# mm16.net
KiCad netlist of a schematic drawn in EAGLE
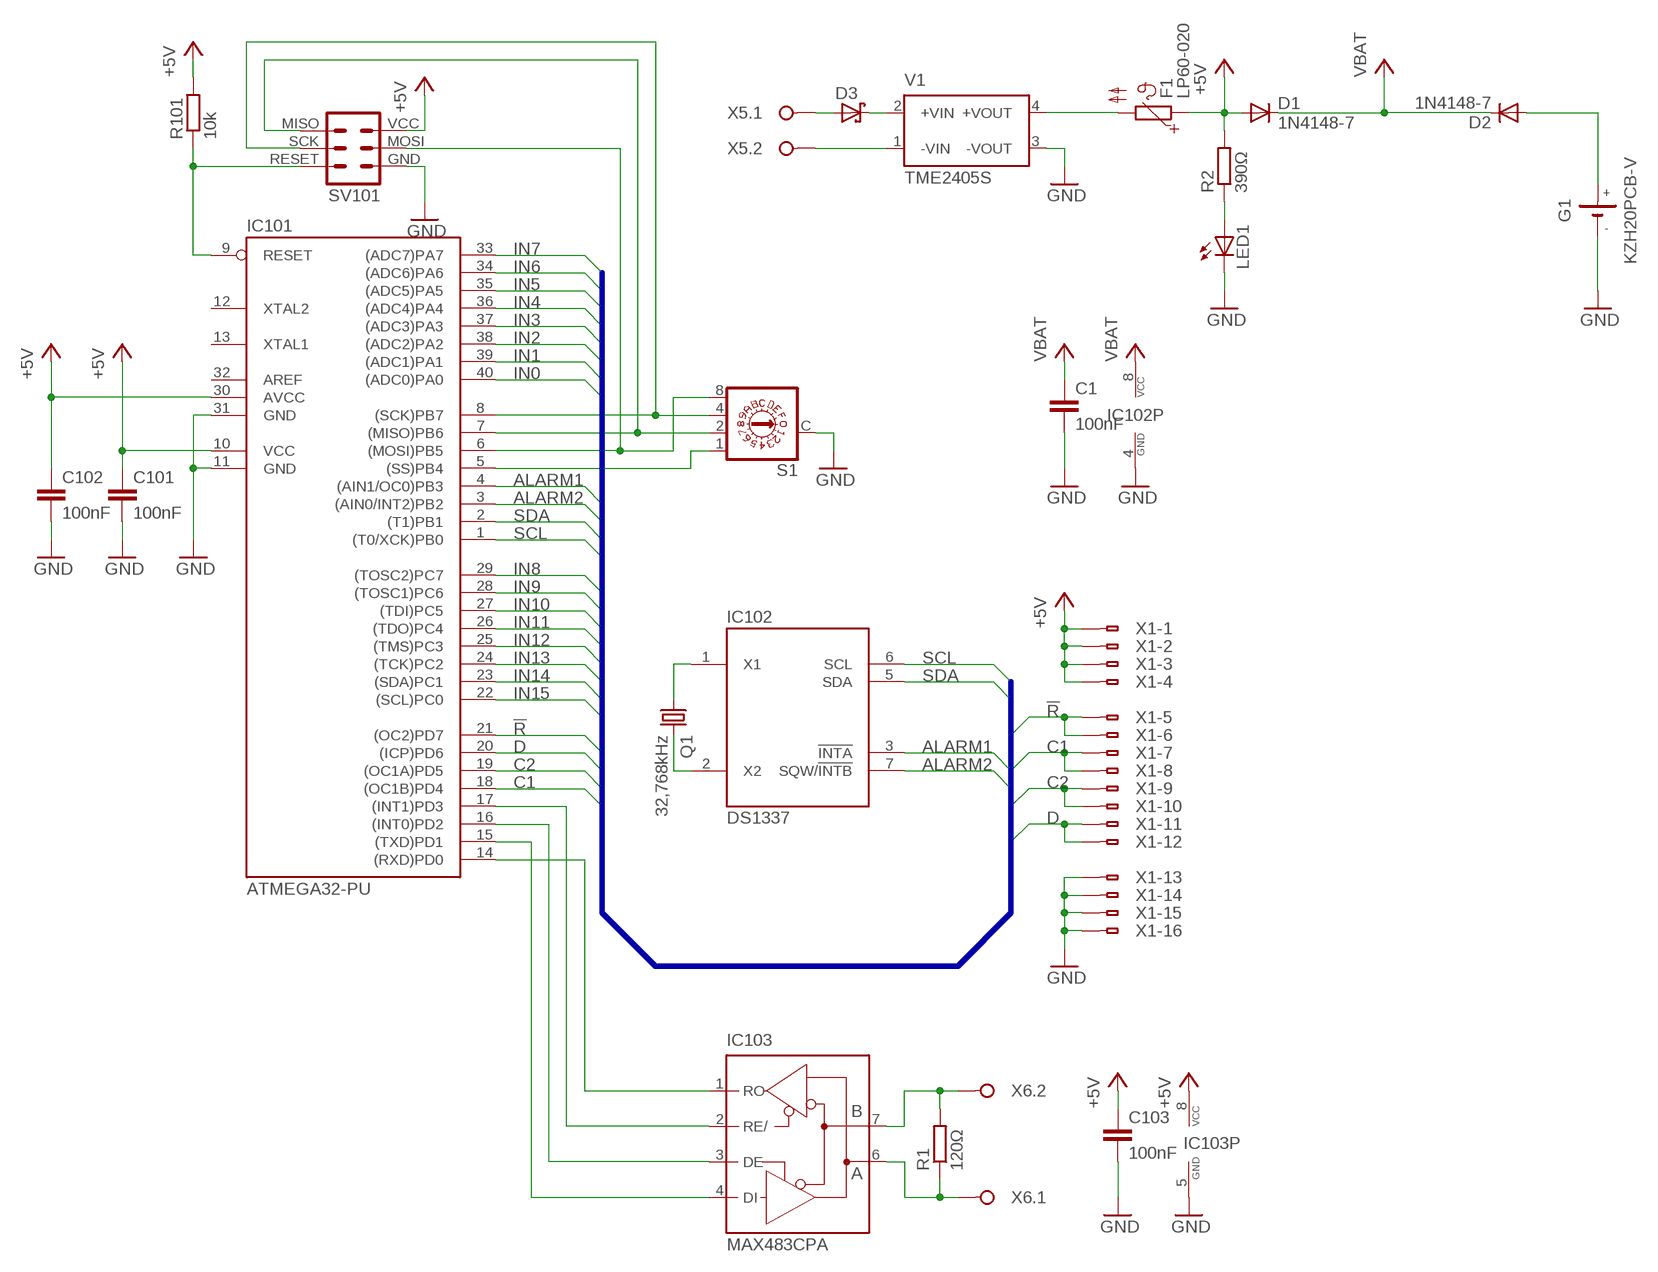
[diagram p0: schematic, sheet 1]
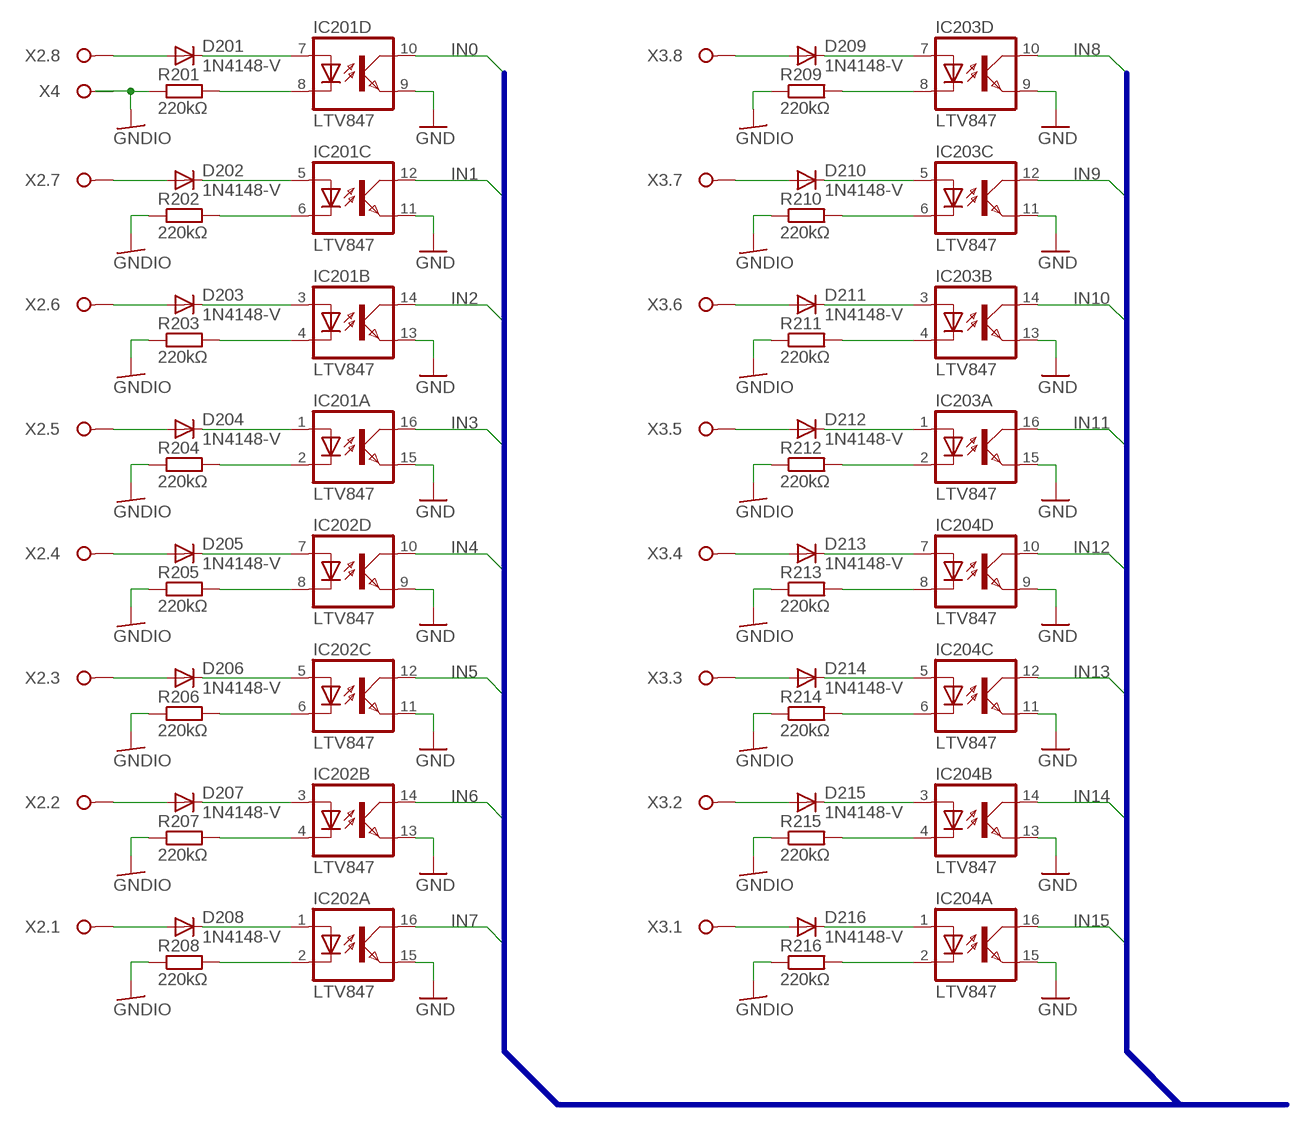
[diagram p1: schematic, sheet 2]

(export (version "E")
  (design (tool "Eeschema 10.0.6"))
  (components
    (comp (ref "C1")
      (value "100nF")
      (footprint "eagle-import:C025-025X050")
      (libsource (lib "eagle-import") (part "C_025-025X050"))
    )
    (comp (ref "C101")
      (value "100nF")
      (footprint "eagle-import:C025-025X050")
      (libsource (lib "eagle-import") (part "C_025-025X050"))
    )
    (comp (ref "C102")
      (value "100nF")
      (footprint "eagle-import:C025-025X050")
      (libsource (lib "eagle-import") (part "C_025-025X050"))
    )
    (comp (ref "C103")
      (value "100nF")
      (footprint "eagle-import:C025-025X050")
      (libsource (lib "eagle-import") (part "C_025-025X050"))
    )
    (comp (ref "D1")
      (value "1N4148-7")
      (footprint "eagle-import:DO35-7@1")
      (libsource (lib "eagle-import") (part "1N4148-7"))
    )
    (comp (ref "D2")
      (value "1N4148-7")
      (footprint "eagle-import:DO35-7@1")
      (libsource (lib "eagle-import") (part "1N4148-7"))
    )
    (comp (ref "D3")
      (value "SCHOTTKY-DIODEDO35-7")
      (footprint "eagle-import:DO35-7")
      (libsource (lib "eagle-import") (part "SCHOTTKY-DIODEDO35-7"))
    )
    (comp (ref "F1")
      (value "LP60-020")
      (footprint "eagle-import:LP60-020")
      (libsource (lib "eagle-import") (part "LP60-020"))
    )
    (comp (ref "G1")
      (value "KZH20PCB-V")
      (footprint "eagle-import:KZH20PCB-V")
      (libsource (lib "eagle-import") (part "KZH20PCB-V"))
    )
    (comp (ref "IC101")
      (value "ATMEGA32-PU")
      (footprint "eagle-import:DIL40")
      (libsource (lib "eagle-import") (part "ATMEGA32-PU"))
    )
    (comp (ref "IC102")
      (value "DS1337")
      (footprint "eagle-import:DIL08")
      (libsource (lib "eagle-import") (part "DS1337"))
    )
    (comp (ref "IC103")
      (value "MAX483CPA")
      (footprint "eagle-import:DIL08")
      (libsource (lib "eagle-import") (part "MAX48CPA3"))
    )
    (comp (ref "LED1")
      (value "LED3MM")
      (footprint "eagle-import:LED3MM")
      (libsource (lib "eagle-import") (part "LED3MM"))
    )
    (comp (ref "Q1")
      (value "32,768kHz")
      (footprint "eagle-import:TC38H")
      (libsource (lib "eagle-import") (part "Q_TC38H"))
    )
    (comp (ref "R1")
      (value "120Ω")
      (footprint "eagle-import:0204V")
      (libsource (lib "eagle-import") (part "R_0204/2V"))
    )
    (comp (ref "R2")
      (value "390Ω")
      (footprint "eagle-import:0204V")
      (libsource (lib "eagle-import") (part "R_0204/2V"))
    )
    (comp (ref "R101")
      (value "10k")
      (footprint "eagle-import:0204V")
      (libsource (lib "eagle-import") (part "R_0204/2V"))
    )
    (comp (ref "S1")
      (value "P103")
      (footprint "eagle-import:P103")
      (libsource (lib "eagle-import") (part "P103"))
    )
    (comp (ref "SV101")
      (value "AVR_ISP6")
      (footprint "eagle-import:ML6")
      (libsource (lib "eagle-import") (part "AVR_ISP6"))
    )
    (comp (ref "V1")
      (value "TME2405S")
      (footprint "eagle-import:TME-24V")
      (fields
        (field (name "MPN") "TME 2405S")
        (field (name "MPN_1") "TME 2405S")
        (field (name "OC_FARNELL") "1007547")
        (field (name "OC_NEWARK") "51R5329")
      )
      (libsource (lib "eagle-import") (part "TME?2405S"))
    )
    (comp (ref "X1")
      (value "WS16V")
      (footprint "eagle-import:WS16V")
      (libsource (lib "eagle-import") (part "WS16V"))
    )
    (comp (ref "X5")
      (value "WAGO_236-402")
      (footprint "eagle-import:WAGO_236-402")
      (libsource (lib "eagle-import") (part "WAGO_236-402"))
    )
    (comp (ref "X6")
      (value "WAGO_236-402")
      (footprint "eagle-import:WAGO_236-402")
      (libsource (lib "eagle-import") (part "WAGO_236-402"))
    )
    (comp (ref "D201")
      (value "1N4148-V")
      (footprint "eagle-import:DO35-V")
      (libsource (lib "eagle-import") (part "1N4148-V"))
    )
    (comp (ref "D202")
      (value "1N4148-V")
      (footprint "eagle-import:DO35-V")
      (libsource (lib "eagle-import") (part "1N4148-V"))
    )
    (comp (ref "D203")
      (value "1N4148-V")
      (footprint "eagle-import:DO35-V")
      (libsource (lib "eagle-import") (part "1N4148-V"))
    )
    (comp (ref "D204")
      (value "1N4148-V")
      (footprint "eagle-import:DO35-V")
      (libsource (lib "eagle-import") (part "1N4148-V"))
    )
    (comp (ref "D205")
      (value "1N4148-V")
      (footprint "eagle-import:DO35-V")
      (libsource (lib "eagle-import") (part "1N4148-V"))
    )
    (comp (ref "D206")
      (value "1N4148-V")
      (footprint "eagle-import:DO35-V")
      (libsource (lib "eagle-import") (part "1N4148-V"))
    )
    (comp (ref "D207")
      (value "1N4148-V")
      (footprint "eagle-import:DO35-V")
      (libsource (lib "eagle-import") (part "1N4148-V"))
    )
    (comp (ref "D208")
      (value "1N4148-V")
      (footprint "eagle-import:DO35-V")
      (libsource (lib "eagle-import") (part "1N4148-V"))
    )
    (comp (ref "D209")
      (value "1N4148-V")
      (footprint "eagle-import:DO35-V")
      (libsource (lib "eagle-import") (part "1N4148-V"))
    )
    (comp (ref "D210")
      (value "1N4148-V")
      (footprint "eagle-import:DO35-V")
      (libsource (lib "eagle-import") (part "1N4148-V"))
    )
    (comp (ref "D211")
      (value "1N4148-V")
      (footprint "eagle-import:DO35-V")
      (libsource (lib "eagle-import") (part "1N4148-V"))
    )
    (comp (ref "D212")
      (value "1N4148-V")
      (footprint "eagle-import:DO35-V")
      (libsource (lib "eagle-import") (part "1N4148-V"))
    )
    (comp (ref "D213")
      (value "1N4148-V")
      (footprint "eagle-import:DO35-V")
      (libsource (lib "eagle-import") (part "1N4148-V"))
    )
    (comp (ref "D214")
      (value "1N4148-V")
      (footprint "eagle-import:DO35-V")
      (libsource (lib "eagle-import") (part "1N4148-V"))
    )
    (comp (ref "D215")
      (value "1N4148-V")
      (footprint "eagle-import:DO35-V")
      (libsource (lib "eagle-import") (part "1N4148-V"))
    )
    (comp (ref "D216")
      (value "1N4148-V")
      (footprint "eagle-import:DO35-V")
      (libsource (lib "eagle-import") (part "1N4148-V"))
    )
    (comp (ref "IC201")
      (value "LTV847")
      (footprint "eagle-import:DIL16")
      (libsource (lib "eagle-import") (part "LTV847"))
    )
    (comp (ref "IC202")
      (value "LTV847")
      (footprint "eagle-import:DIL16")
      (libsource (lib "eagle-import") (part "LTV847"))
    )
    (comp (ref "IC203")
      (value "LTV847")
      (footprint "eagle-import:DIL16")
      (libsource (lib "eagle-import") (part "LTV847"))
    )
    (comp (ref "IC204")
      (value "LTV847")
      (footprint "eagle-import:DIL16")
      (libsource (lib "eagle-import") (part "LTV847"))
    )
    (comp (ref "R201")
      (value "220kΩ")
      (footprint "eagle-import:0204V")
      (libsource (lib "eagle-import") (part "R_0204/2V"))
    )
    (comp (ref "R202")
      (value "220kΩ")
      (footprint "eagle-import:0204V")
      (libsource (lib "eagle-import") (part "R_0204/2V"))
    )
    (comp (ref "R203")
      (value "220kΩ")
      (footprint "eagle-import:0204V")
      (libsource (lib "eagle-import") (part "R_0204/2V"))
    )
    (comp (ref "R204")
      (value "220kΩ")
      (footprint "eagle-import:0204V")
      (libsource (lib "eagle-import") (part "R_0204/2V"))
    )
    (comp (ref "R205")
      (value "220kΩ")
      (footprint "eagle-import:0204V")
      (libsource (lib "eagle-import") (part "R_0204/2V"))
    )
    (comp (ref "R206")
      (value "220kΩ")
      (footprint "eagle-import:0204V")
      (libsource (lib "eagle-import") (part "R_0204/2V"))
    )
    (comp (ref "R207")
      (value "220kΩ")
      (footprint "eagle-import:0204V")
      (libsource (lib "eagle-import") (part "R_0204/2V"))
    )
    (comp (ref "R208")
      (value "220kΩ")
      (footprint "eagle-import:0204V")
      (libsource (lib "eagle-import") (part "R_0204/2V"))
    )
    (comp (ref "R209")
      (value "220kΩ")
      (footprint "eagle-import:0204V")
      (libsource (lib "eagle-import") (part "R_0204/2V"))
    )
    (comp (ref "R210")
      (value "220kΩ")
      (footprint "eagle-import:0204V")
      (libsource (lib "eagle-import") (part "R_0204/2V"))
    )
    (comp (ref "R211")
      (value "220kΩ")
      (footprint "eagle-import:0204V")
      (libsource (lib "eagle-import") (part "R_0204/2V"))
    )
    (comp (ref "R212")
      (value "220kΩ")
      (footprint "eagle-import:0204V")
      (libsource (lib "eagle-import") (part "R_0204/2V"))
    )
    (comp (ref "R213")
      (value "220kΩ")
      (footprint "eagle-import:0204V")
      (libsource (lib "eagle-import") (part "R_0204/2V"))
    )
    (comp (ref "R214")
      (value "220kΩ")
      (footprint "eagle-import:0204V")
      (libsource (lib "eagle-import") (part "R_0204/2V"))
    )
    (comp (ref "R215")
      (value "220kΩ")
      (footprint "eagle-import:0204V")
      (libsource (lib "eagle-import") (part "R_0204/2V"))
    )
    (comp (ref "R216")
      (value "220kΩ")
      (footprint "eagle-import:0204V")
      (libsource (lib "eagle-import") (part "R_0204/2V"))
    )
    (comp (ref "X2")
      (value "WAGO_236-408")
      (footprint "eagle-import:WAGO_236-408")
      (libsource (lib "eagle-import") (part "WAGO_236-408"))
    )
    (comp (ref "X3")
      (value "WAGO_236-408")
      (footprint "eagle-import:WAGO_236-408")
      (libsource (lib "eagle-import") (part "WAGO_236-408"))
    )
    (comp (ref "X4")
      (value "WAGO_236-401")
      (footprint "eagle-import:WAGO_236-401")
      (libsource (lib "eagle-import") (part "WAGO_236-401"))
    )
  )
  (nets
    (net (code "1") (name "+5V") (class "Default")
      (node (ref "C101") (pin "1") (pinfunction "1_1") (pintype "passive"))
      (node (ref "C102") (pin "1") (pinfunction "1_1") (pintype "passive"))
      (node (ref "C103") (pin "1") (pinfunction "1_1") (pintype "passive"))
      (node (ref "D1") (pin "A") (pinfunction "A_A") (pintype "passive"))
      (node (ref "F1") (pin "P$1") (pinfunction "1_P$1") (pintype "passive"))
      (node (ref "IC101") (pin "10") (pinfunction "VCC_10") (pintype "power_in"))
      (node (ref "IC101") (pin "30") (pinfunction "AVCC_30") (pintype "power_in"))
      (node (ref "IC103") (pin "8") (pinfunction "VCC_8") (pintype "power_in"))
      (node (ref "R101") (pin "2") (pinfunction "2_2") (pintype "passive"))
      (node (ref "R2") (pin "2") (pinfunction "2_2") (pintype "passive"))
      (node (ref "SV101") (pin "VCC") (pinfunction "VCC_VCC") (pintype "passive"))
      (node (ref "X1") (pin "1") (pinfunction "A_1") (pintype "passive"))
      (node (ref "X1") (pin "2") (pinfunction "A_2") (pintype "passive"))
      (node (ref "X1") (pin "3") (pinfunction "A_3") (pintype "passive"))
      (node (ref "X1") (pin "4") (pinfunction "A_4") (pintype "passive"))
    )
    (net (code "2") (name "ALARM1") (class "Default")
      (node (ref "IC101") (pin "4") (pinfunction "(AIN1/OC0)PB3_4") (pintype "bidirectional"))
      (node (ref "IC102") (pin "3") (pinfunction "~{INTA}_3") (pintype "open_collector"))
    )
    (net (code "3") (name "ALARM2") (class "Default")
      (node (ref "IC101") (pin "3") (pinfunction "(AIN0/INT2)PB2_3") (pintype "bidirectional"))
      (node (ref "IC102") (pin "7") (pinfunction "SQW/~{INTB}_7") (pintype "open_collector"))
    )
    (net (code "4") (name "C1") (class "Default")
      (node (ref "IC101") (pin "18") (pinfunction "(OC1B)PD4_18") (pintype "bidirectional"))
      (node (ref "X1") (pin "7") (pinfunction "A_7") (pintype "passive"))
      (node (ref "X1") (pin "8") (pinfunction "A_8") (pintype "passive"))
    )
    (net (code "5") (name "C2") (class "Default")
      (node (ref "IC101") (pin "19") (pinfunction "(OC1A)PD5_19") (pintype "bidirectional"))
      (node (ref "X1") (pin "10") (pinfunction "A_10") (pintype "passive"))
      (node (ref "X1") (pin "9") (pinfunction "A_9") (pintype "passive"))
    )
    (net (code "6") (name "D") (class "Default")
      (node (ref "IC101") (pin "20") (pinfunction "(ICP)PD6_20") (pintype "bidirectional"))
      (node (ref "X1") (pin "11") (pinfunction "A_11") (pintype "passive"))
      (node (ref "X1") (pin "12") (pinfunction "A_12") (pintype "passive"))
    )
    (net (code "7") (name "GND") (class "Default")
      (node (ref "C1") (pin "2") (pinfunction "2_2") (pintype "passive"))
      (node (ref "C101") (pin "2") (pinfunction "2_2") (pintype "passive"))
      (node (ref "C102") (pin "2") (pinfunction "2_2") (pintype "passive"))
      (node (ref "C103") (pin "2") (pinfunction "2_2") (pintype "passive"))
      (node (ref "G1") (pin "-") (pinfunction "-_-") (pintype "passive"))
      (node (ref "IC101") (pin "11") (pinfunction "GND_11") (pintype "power_in"))
      (node (ref "IC101") (pin "31") (pinfunction "GND_31") (pintype "power_in"))
      (node (ref "IC102") (pin "4") (pinfunction "GND_4") (pintype "power_in"))
      (node (ref "IC103") (pin "5") (pinfunction "GND_5") (pintype "power_in"))
      (node (ref "IC201") (pin "11") (pinfunction "EMIT_11") (pintype "passive"))
      (node (ref "IC201") (pin "13") (pinfunction "EMIT_13") (pintype "passive"))
      (node (ref "IC201") (pin "15") (pinfunction "EMIT_15") (pintype "passive"))
      (node (ref "IC201") (pin "9") (pinfunction "EMIT_9") (pintype "passive"))
      (node (ref "IC202") (pin "11") (pinfunction "EMIT_11") (pintype "passive"))
      (node (ref "IC202") (pin "13") (pinfunction "EMIT_13") (pintype "passive"))
      (node (ref "IC202") (pin "15") (pinfunction "EMIT_15") (pintype "passive"))
      (node (ref "IC202") (pin "9") (pinfunction "EMIT_9") (pintype "passive"))
      (node (ref "IC203") (pin "11") (pinfunction "EMIT_11") (pintype "passive"))
      (node (ref "IC203") (pin "13") (pinfunction "EMIT_13") (pintype "passive"))
      (node (ref "IC203") (pin "15") (pinfunction "EMIT_15") (pintype "passive"))
      (node (ref "IC203") (pin "9") (pinfunction "EMIT_9") (pintype "passive"))
      (node (ref "IC204") (pin "11") (pinfunction "EMIT_11") (pintype "passive"))
      (node (ref "IC204") (pin "13") (pinfunction "EMIT_13") (pintype "passive"))
      (node (ref "IC204") (pin "15") (pinfunction "EMIT_15") (pintype "passive"))
      (node (ref "IC204") (pin "9") (pinfunction "EMIT_9") (pintype "passive"))
      (node (ref "LED1") (pin "K") (pinfunction "C_K") (pintype "passive"))
      (node (ref "S1") (pin "C") (pinfunction "C_C") (pintype "passive"))
      (node (ref "SV101") (pin "GND") (pinfunction "GND_GND") (pintype "passive"))
      (node (ref "V1") (pin "3") (pinfunction "-VOUT_3") (pintype "passive"))
      (node (ref "X1") (pin "13") (pinfunction "A_13") (pintype "passive"))
      (node (ref "X1") (pin "14") (pinfunction "A_14") (pintype "passive"))
      (node (ref "X1") (pin "15") (pinfunction "A_15") (pintype "passive"))
      (node (ref "X1") (pin "16") (pinfunction "A_16") (pintype "passive"))
    )
    (net (code "8") (name "GNDIO") (class "Default")
      (node (ref "R201") (pin "1") (pinfunction "1_1") (pintype "passive"))
      (node (ref "R202") (pin "1") (pinfunction "1_1") (pintype "passive"))
      (node (ref "R203") (pin "1") (pinfunction "1_1") (pintype "passive"))
      (node (ref "R204") (pin "1") (pinfunction "1_1") (pintype "passive"))
      (node (ref "R205") (pin "1") (pinfunction "1_1") (pintype "passive"))
      (node (ref "R206") (pin "1") (pinfunction "1_1") (pintype "passive"))
      (node (ref "R207") (pin "1") (pinfunction "1_1") (pintype "passive"))
      (node (ref "R208") (pin "1") (pinfunction "1_1") (pintype "passive"))
      (node (ref "R209") (pin "1") (pinfunction "1_1") (pintype "passive"))
      (node (ref "R210") (pin "1") (pinfunction "1_1") (pintype "passive"))
      (node (ref "R211") (pin "1") (pinfunction "1_1") (pintype "passive"))
      (node (ref "R212") (pin "1") (pinfunction "1_1") (pintype "passive"))
      (node (ref "R213") (pin "1") (pinfunction "1_1") (pintype "passive"))
      (node (ref "R214") (pin "1") (pinfunction "1_1") (pintype "passive"))
      (node (ref "R215") (pin "1") (pinfunction "1_1") (pintype "passive"))
      (node (ref "R216") (pin "1") (pinfunction "1_1") (pintype "passive"))
      (node (ref "X4") (pin "A1") (pinfunction "A_A1") (pintype "passive"))
      (node (ref "X4") (pin "B1") (pinfunction "B_B1") (pintype "passive"))
    )
    (net (code "9") (name "IN0") (class "Default")
      (node (ref "IC101") (pin "40") (pinfunction "(ADC0)PA0_40") (pintype "bidirectional"))
      (node (ref "IC201") (pin "10") (pinfunction "COL_10") (pintype "passive"))
    )
    (net (code "10") (name "IN1") (class "Default")
      (node (ref "IC101") (pin "39") (pinfunction "(ADC1)PA1_39") (pintype "bidirectional"))
      (node (ref "IC201") (pin "12") (pinfunction "COL_12") (pintype "passive"))
    )
    (net (code "11") (name "IN2") (class "Default")
      (node (ref "IC101") (pin "38") (pinfunction "(ADC2)PA2_38") (pintype "bidirectional"))
      (node (ref "IC201") (pin "14") (pinfunction "COL_14") (pintype "passive"))
    )
    (net (code "12") (name "IN3") (class "Default")
      (node (ref "IC101") (pin "37") (pinfunction "(ADC3)PA3_37") (pintype "bidirectional"))
      (node (ref "IC201") (pin "16") (pinfunction "COL_16") (pintype "passive"))
    )
    (net (code "13") (name "IN4") (class "Default")
      (node (ref "IC101") (pin "36") (pinfunction "(ADC4)PA4_36") (pintype "bidirectional"))
      (node (ref "IC202") (pin "10") (pinfunction "COL_10") (pintype "passive"))
    )
    (net (code "14") (name "IN5") (class "Default")
      (node (ref "IC101") (pin "35") (pinfunction "(ADC5)PA5_35") (pintype "bidirectional"))
      (node (ref "IC202") (pin "12") (pinfunction "COL_12") (pintype "passive"))
    )
    (net (code "15") (name "IN6") (class "Default")
      (node (ref "IC101") (pin "34") (pinfunction "(ADC6)PA6_34") (pintype "bidirectional"))
      (node (ref "IC202") (pin "14") (pinfunction "COL_14") (pintype "passive"))
    )
    (net (code "16") (name "IN7") (class "Default")
      (node (ref "IC101") (pin "33") (pinfunction "(ADC7)PA7_33") (pintype "bidirectional"))
      (node (ref "IC202") (pin "16") (pinfunction "COL_16") (pintype "passive"))
    )
    (net (code "17") (name "IN8") (class "Default")
      (node (ref "IC101") (pin "29") (pinfunction "(TOSC2)PC7_29") (pintype "bidirectional"))
      (node (ref "IC203") (pin "10") (pinfunction "COL_10") (pintype "passive"))
    )
    (net (code "18") (name "IN9") (class "Default")
      (node (ref "IC101") (pin "28") (pinfunction "(TOSC1)PC6_28") (pintype "bidirectional"))
      (node (ref "IC203") (pin "12") (pinfunction "COL_12") (pintype "passive"))
    )
    (net (code "19") (name "IN10") (class "Default")
      (node (ref "IC101") (pin "27") (pinfunction "(TDI)PC5_27") (pintype "bidirectional"))
      (node (ref "IC203") (pin "14") (pinfunction "COL_14") (pintype "passive"))
    )
    (net (code "20") (name "IN11") (class "Default")
      (node (ref "IC101") (pin "26") (pinfunction "(TDO)PC4_26") (pintype "bidirectional"))
      (node (ref "IC203") (pin "16") (pinfunction "COL_16") (pintype "passive"))
    )
    (net (code "21") (name "IN12") (class "Default")
      (node (ref "IC101") (pin "25") (pinfunction "(TMS)PC3_25") (pintype "bidirectional"))
      (node (ref "IC204") (pin "10") (pinfunction "COL_10") (pintype "passive"))
    )
    (net (code "22") (name "IN13") (class "Default")
      (node (ref "IC101") (pin "24") (pinfunction "(TCK)PC2_24") (pintype "bidirectional"))
      (node (ref "IC204") (pin "12") (pinfunction "COL_12") (pintype "passive"))
    )
    (net (code "23") (name "IN14") (class "Default")
      (node (ref "IC101") (pin "23") (pinfunction "(SDA)PC1_23") (pintype "bidirectional"))
      (node (ref "IC204") (pin "14") (pinfunction "COL_14") (pintype "passive"))
    )
    (net (code "24") (name "IN15") (class "Default")
      (node (ref "IC101") (pin "22") (pinfunction "(SCL)PC0_22") (pintype "bidirectional"))
      (node (ref "IC204") (pin "16") (pinfunction "COL_16") (pintype "passive"))
    )
    (net (code "25") (name "Net-(D2-PadA)") (class "Default")
      (node (ref "D2") (pin "A") (pinfunction "A_A") (pintype "passive"))
      (node (ref "G1") (pin "+1") (pinfunction "+_+1") (pintype "passive"))
      (node (ref "G1") (pin "+2") (pinfunction "+_+2") (pintype "passive"))
    )
    (net (code "26") (name "Net-(D3-PadA)") (class "Default")
      (node (ref "D3") (pin "A") (pinfunction "A_A") (pintype "passive"))
      (node (ref "X5") (pin "A1") (pinfunction "A_A1") (pintype "passive"))
      (node (ref "X5") (pin "B1") (pinfunction "A_B1") (pintype "passive"))
    )
    (net (code "27") (name "Net-(D201-A)") (class "Default")
      (node (ref "D201") (pin "1") (pinfunction "A_1") (pintype "passive"))
      (node (ref "X2") (pin "A8") (pinfunction "A_A8") (pintype "passive"))
      (node (ref "X2") (pin "B8") (pinfunction "A_B8") (pintype "passive"))
    )
    (net (code "28") (name "Net-(D201-C)") (class "Default")
      (node (ref "D201") (pin "2") (pinfunction "C_2") (pintype "passive"))
      (node (ref "IC201") (pin "7") (pinfunction "A_7") (pintype "passive"))
    )
    (net (code "29") (name "Net-(D202-A)") (class "Default")
      (node (ref "D202") (pin "1") (pinfunction "A_1") (pintype "passive"))
      (node (ref "X2") (pin "A7") (pinfunction "A_A7") (pintype "passive"))
      (node (ref "X2") (pin "B7") (pinfunction "A_B7") (pintype "passive"))
    )
    (net (code "30") (name "Net-(D202-C)") (class "Default")
      (node (ref "D202") (pin "2") (pinfunction "C_2") (pintype "passive"))
      (node (ref "IC201") (pin "5") (pinfunction "A_5") (pintype "passive"))
    )
    (net (code "31") (name "Net-(D203-A)") (class "Default")
      (node (ref "D203") (pin "1") (pinfunction "A_1") (pintype "passive"))
      (node (ref "X2") (pin "A6") (pinfunction "A_A6") (pintype "passive"))
      (node (ref "X2") (pin "B6") (pinfunction "A_B6") (pintype "passive"))
    )
    (net (code "32") (name "Net-(D203-C)") (class "Default")
      (node (ref "D203") (pin "2") (pinfunction "C_2") (pintype "passive"))
      (node (ref "IC201") (pin "3") (pinfunction "A_3") (pintype "passive"))
    )
    (net (code "33") (name "Net-(D204-A)") (class "Default")
      (node (ref "D204") (pin "1") (pinfunction "A_1") (pintype "passive"))
      (node (ref "X2") (pin "A5") (pinfunction "A_A5") (pintype "passive"))
      (node (ref "X2") (pin "B5") (pinfunction "A_B5") (pintype "passive"))
    )
    (net (code "34") (name "Net-(D204-C)") (class "Default")
      (node (ref "D204") (pin "2") (pinfunction "C_2") (pintype "passive"))
      (node (ref "IC201") (pin "1") (pinfunction "A_1") (pintype "passive"))
    )
    (net (code "35") (name "Net-(D205-A)") (class "Default")
      (node (ref "D205") (pin "1") (pinfunction "A_1") (pintype "passive"))
      (node (ref "X2") (pin "A4") (pinfunction "A_A4") (pintype "passive"))
      (node (ref "X2") (pin "B4") (pinfunction "A_B4") (pintype "passive"))
    )
    (net (code "36") (name "Net-(D205-C)") (class "Default")
      (node (ref "D205") (pin "2") (pinfunction "C_2") (pintype "passive"))
      (node (ref "IC202") (pin "7") (pinfunction "A_7") (pintype "passive"))
    )
    (net (code "37") (name "Net-(D206-A)") (class "Default")
      (node (ref "D206") (pin "1") (pinfunction "A_1") (pintype "passive"))
      (node (ref "X2") (pin "A3") (pinfunction "A_A3") (pintype "passive"))
      (node (ref "X2") (pin "B3") (pinfunction "A_B3") (pintype "passive"))
    )
    (net (code "38") (name "Net-(D206-C)") (class "Default")
      (node (ref "D206") (pin "2") (pinfunction "C_2") (pintype "passive"))
      (node (ref "IC202") (pin "5") (pinfunction "A_5") (pintype "passive"))
    )
    (net (code "39") (name "Net-(D207-A)") (class "Default")
      (node (ref "D207") (pin "1") (pinfunction "A_1") (pintype "passive"))
      (node (ref "X2") (pin "A2") (pinfunction "A_A2") (pintype "passive"))
      (node (ref "X2") (pin "B2") (pinfunction "A_B2") (pintype "passive"))
    )
    (net (code "40") (name "Net-(D207-C)") (class "Default")
      (node (ref "D207") (pin "2") (pinfunction "C_2") (pintype "passive"))
      (node (ref "IC202") (pin "3") (pinfunction "A_3") (pintype "passive"))
    )
    (net (code "41") (name "Net-(D208-A)") (class "Default")
      (node (ref "D208") (pin "1") (pinfunction "A_1") (pintype "passive"))
      (node (ref "X2") (pin "A1") (pinfunction "A_A1") (pintype "passive"))
      (node (ref "X2") (pin "B1") (pinfunction "A_B1") (pintype "passive"))
    )
    (net (code "42") (name "Net-(D208-C)") (class "Default")
      (node (ref "D208") (pin "2") (pinfunction "C_2") (pintype "passive"))
      (node (ref "IC202") (pin "1") (pinfunction "A_1") (pintype "passive"))
    )
    (net (code "43") (name "Net-(D209-A)") (class "Default")
      (node (ref "D209") (pin "1") (pinfunction "A_1") (pintype "passive"))
      (node (ref "X3") (pin "A8") (pinfunction "A_A8") (pintype "passive"))
      (node (ref "X3") (pin "B8") (pinfunction "A_B8") (pintype "passive"))
    )
    (net (code "44") (name "Net-(D209-C)") (class "Default")
      (node (ref "D209") (pin "2") (pinfunction "C_2") (pintype "passive"))
      (node (ref "IC203") (pin "7") (pinfunction "A_7") (pintype "passive"))
    )
    (net (code "45") (name "Net-(D210-A)") (class "Default")
      (node (ref "D210") (pin "1") (pinfunction "A_1") (pintype "passive"))
      (node (ref "X3") (pin "A7") (pinfunction "A_A7") (pintype "passive"))
      (node (ref "X3") (pin "B7") (pinfunction "A_B7") (pintype "passive"))
    )
    (net (code "46") (name "Net-(D210-C)") (class "Default")
      (node (ref "D210") (pin "2") (pinfunction "C_2") (pintype "passive"))
      (node (ref "IC203") (pin "5") (pinfunction "A_5") (pintype "passive"))
    )
    (net (code "47") (name "Net-(D211-A)") (class "Default")
      (node (ref "D211") (pin "1") (pinfunction "A_1") (pintype "passive"))
      (node (ref "X3") (pin "A6") (pinfunction "A_A6") (pintype "passive"))
      (node (ref "X3") (pin "B6") (pinfunction "A_B6") (pintype "passive"))
    )
    (net (code "48") (name "Net-(D211-C)") (class "Default")
      (node (ref "D211") (pin "2") (pinfunction "C_2") (pintype "passive"))
      (node (ref "IC203") (pin "3") (pinfunction "A_3") (pintype "passive"))
    )
    (net (code "49") (name "Net-(D212-A)") (class "Default")
      (node (ref "D212") (pin "1") (pinfunction "A_1") (pintype "passive"))
      (node (ref "X3") (pin "A5") (pinfunction "A_A5") (pintype "passive"))
      (node (ref "X3") (pin "B5") (pinfunction "A_B5") (pintype "passive"))
    )
    (net (code "50") (name "Net-(D212-C)") (class "Default")
      (node (ref "D212") (pin "2") (pinfunction "C_2") (pintype "passive"))
      (node (ref "IC203") (pin "1") (pinfunction "A_1") (pintype "passive"))
    )
    (net (code "51") (name "Net-(D213-A)") (class "Default")
      (node (ref "D213") (pin "1") (pinfunction "A_1") (pintype "passive"))
      (node (ref "X3") (pin "A4") (pinfunction "A_A4") (pintype "passive"))
      (node (ref "X3") (pin "B4") (pinfunction "A_B4") (pintype "passive"))
    )
    (net (code "52") (name "Net-(D213-C)") (class "Default")
      (node (ref "D213") (pin "2") (pinfunction "C_2") (pintype "passive"))
      (node (ref "IC204") (pin "7") (pinfunction "A_7") (pintype "passive"))
    )
    (net (code "53") (name "Net-(D214-A)") (class "Default")
      (node (ref "D214") (pin "1") (pinfunction "A_1") (pintype "passive"))
      (node (ref "X3") (pin "A3") (pinfunction "A_A3") (pintype "passive"))
      (node (ref "X3") (pin "B3") (pinfunction "A_B3") (pintype "passive"))
    )
    (net (code "54") (name "Net-(D214-C)") (class "Default")
      (node (ref "D214") (pin "2") (pinfunction "C_2") (pintype "passive"))
      (node (ref "IC204") (pin "5") (pinfunction "A_5") (pintype "passive"))
    )
    (net (code "55") (name "Net-(D215-A)") (class "Default")
      (node (ref "D215") (pin "1") (pinfunction "A_1") (pintype "passive"))
      (node (ref "X3") (pin "A2") (pinfunction "A_A2") (pintype "passive"))
      (node (ref "X3") (pin "B2") (pinfunction "A_B2") (pintype "passive"))
    )
    (net (code "56") (name "Net-(D215-C)") (class "Default")
      (node (ref "D215") (pin "2") (pinfunction "C_2") (pintype "passive"))
      (node (ref "IC204") (pin "3") (pinfunction "A_3") (pintype "passive"))
    )
    (net (code "57") (name "Net-(D216-A)") (class "Default")
      (node (ref "D216") (pin "1") (pinfunction "A_1") (pintype "passive"))
      (node (ref "X3") (pin "A1") (pinfunction "A_A1") (pintype "passive"))
      (node (ref "X3") (pin "B1") (pinfunction "A_B1") (pintype "passive"))
    )
    (net (code "58") (name "Net-(D216-C)") (class "Default")
      (node (ref "D216") (pin "2") (pinfunction "C_2") (pintype "passive"))
      (node (ref "IC204") (pin "1") (pinfunction "A_1") (pintype "passive"))
    )
    (net (code "59") (name "Net-(F1-2)") (class "Default")
      (node (ref "F1") (pin "P$2") (pinfunction "2_P$2") (pintype "passive"))
      (node (ref "V1") (pin "4") (pinfunction "+VOUT_4") (pintype "passive"))
    )
    (net (code "60") (name "Net-(IC101-(INT0)PD2)") (class "Default")
      (node (ref "IC101") (pin "16") (pinfunction "(INT0)PD2_16") (pintype "bidirectional"))
      (node (ref "IC103") (pin "3") (pinfunction "DE_3") (pintype "input"))
    )
    (net (code "61") (name "Net-(IC101-(INT1)PD3)") (class "Default")
      (node (ref "IC101") (pin "17") (pinfunction "(INT1)PD3_17") (pintype "bidirectional"))
      (node (ref "IC103") (pin "2") (pinfunction "RE/_2") (pintype "input"))
    )
    (net (code "62") (name "Net-(IC101-(MISO)PB6)") (class "Default")
      (node (ref "IC101") (pin "7") (pinfunction "(MISO)PB6_7") (pintype "bidirectional"))
      (node (ref "S1") (pin "2") (pinfunction "2_2") (pintype "passive"))
      (node (ref "SV101") (pin "MISO") (pinfunction "MISO_MISO") (pintype "passive"))
    )
    (net (code "63") (name "Net-(IC101-(MOSI)PB5)") (class "Default")
      (node (ref "IC101") (pin "6") (pinfunction "(MOSI)PB5_6") (pintype "bidirectional"))
      (node (ref "S1") (pin "8") (pinfunction "8_8") (pintype "passive"))
      (node (ref "SV101") (pin "MOSI") (pinfunction "MOSI_MOSI") (pintype "passive"))
    )
    (net (code "64") (name "Net-(IC101-(RXD)PD0)") (class "Default")
      (node (ref "IC101") (pin "14") (pinfunction "(RXD)PD0_14") (pintype "bidirectional"))
      (node (ref "IC103") (pin "1") (pinfunction "RO_1") (pintype "output"))
    )
    (net (code "65") (name "Net-(IC101-(SCK)PB7)") (class "Default")
      (node (ref "IC101") (pin "8") (pinfunction "(SCK)PB7_8") (pintype "bidirectional"))
      (node (ref "S1") (pin "4") (pinfunction "4_4") (pintype "passive"))
      (node (ref "SV101") (pin "SCK") (pinfunction "SCK_SCK") (pintype "passive"))
    )
    (net (code "66") (name "Net-(IC101-(SS)PB4)") (class "Default")
      (node (ref "IC101") (pin "5") (pinfunction "(SS)PB4_5") (pintype "bidirectional"))
      (node (ref "S1") (pin "1") (pinfunction "1_1") (pintype "passive"))
    )
    (net (code "67") (name "Net-(IC101-(TXD)PD1)") (class "Default")
      (node (ref "IC101") (pin "15") (pinfunction "(TXD)PD1_15") (pintype "bidirectional"))
      (node (ref "IC103") (pin "4") (pinfunction "DI_4") (pintype "input"))
    )
    (net (code "68") (name "Net-(IC101-RESET)") (class "Default")
      (node (ref "IC101") (pin "9") (pinfunction "RESET_9") (pintype "input"))
      (node (ref "R101") (pin "1") (pinfunction "1_1") (pintype "passive"))
      (node (ref "SV101") (pin "RESET") (pinfunction "RESET_RESET") (pintype "passive"))
    )
    (net (code "69") (name "Net-(IC102A-X1)") (class "Default")
      (node (ref "IC102") (pin "1") (pinfunction "X1_1") (pintype "bidirectional"))
      (node (ref "Q1") (pin "1") (pinfunction "1_1") (pintype "passive"))
    )
    (net (code "70") (name "Net-(IC102A-X2)") (class "Default")
      (node (ref "IC102") (pin "2") (pinfunction "X2_2") (pintype "bidirectional"))
      (node (ref "Q1") (pin "2") (pinfunction "2_2") (pintype "passive"))
    )
    (net (code "71") (name "Net-(IC103A-A)") (class "Default")
      (node (ref "IC103") (pin "6") (pinfunction "A_6") (pintype "passive"))
      (node (ref "R1") (pin "1") (pinfunction "1_1") (pintype "passive"))
      (node (ref "X6") (pin "A1") (pinfunction "A_A1") (pintype "passive"))
      (node (ref "X6") (pin "B1") (pinfunction "A_B1") (pintype "passive"))
    )
    (net (code "72") (name "Net-(IC103A-B)") (class "Default")
      (node (ref "IC103") (pin "7") (pinfunction "B_7") (pintype "passive"))
      (node (ref "R1") (pin "2") (pinfunction "2_2") (pintype "passive"))
      (node (ref "X6") (pin "A2") (pinfunction "A_A2") (pintype "passive"))
      (node (ref "X6") (pin "B2") (pinfunction "A_B2") (pintype "passive"))
    )
    (net (code "73") (name "Net-(IC201A-C)") (class "Default")
      (node (ref "IC201") (pin "2") (pinfunction "C_2") (pintype "passive"))
      (node (ref "R204") (pin "2") (pinfunction "2_2") (pintype "passive"))
    )
    (net (code "74") (name "Net-(IC201B-C)") (class "Default")
      (node (ref "IC201") (pin "4") (pinfunction "C_4") (pintype "passive"))
      (node (ref "R203") (pin "2") (pinfunction "2_2") (pintype "passive"))
    )
    (net (code "75") (name "Net-(IC201C-C)") (class "Default")
      (node (ref "IC201") (pin "6") (pinfunction "C_6") (pintype "passive"))
      (node (ref "R202") (pin "2") (pinfunction "2_2") (pintype "passive"))
    )
    (net (code "76") (name "Net-(IC201D-C)") (class "Default")
      (node (ref "IC201") (pin "8") (pinfunction "C_8") (pintype "passive"))
      (node (ref "R201") (pin "2") (pinfunction "2_2") (pintype "passive"))
    )
    (net (code "77") (name "Net-(IC202A-C)") (class "Default")
      (node (ref "IC202") (pin "2") (pinfunction "C_2") (pintype "passive"))
      (node (ref "R208") (pin "2") (pinfunction "2_2") (pintype "passive"))
    )
    (net (code "78") (name "Net-(IC202B-C)") (class "Default")
      (node (ref "IC202") (pin "4") (pinfunction "C_4") (pintype "passive"))
      (node (ref "R207") (pin "2") (pinfunction "2_2") (pintype "passive"))
    )
    (net (code "79") (name "Net-(IC202C-C)") (class "Default")
      (node (ref "IC202") (pin "6") (pinfunction "C_6") (pintype "passive"))
      (node (ref "R206") (pin "2") (pinfunction "2_2") (pintype "passive"))
    )
    (net (code "80") (name "Net-(IC202D-C)") (class "Default")
      (node (ref "IC202") (pin "8") (pinfunction "C_8") (pintype "passive"))
      (node (ref "R205") (pin "2") (pinfunction "2_2") (pintype "passive"))
    )
    (net (code "81") (name "Net-(IC203A-C)") (class "Default")
      (node (ref "IC203") (pin "2") (pinfunction "C_2") (pintype "passive"))
      (node (ref "R212") (pin "2") (pinfunction "2_2") (pintype "passive"))
    )
    (net (code "82") (name "Net-(IC203B-C)") (class "Default")
      (node (ref "IC203") (pin "4") (pinfunction "C_4") (pintype "passive"))
      (node (ref "R211") (pin "2") (pinfunction "2_2") (pintype "passive"))
    )
    (net (code "83") (name "Net-(IC203C-C)") (class "Default")
      (node (ref "IC203") (pin "6") (pinfunction "C_6") (pintype "passive"))
      (node (ref "R210") (pin "2") (pinfunction "2_2") (pintype "passive"))
    )
    (net (code "84") (name "Net-(IC203D-C)") (class "Default")
      (node (ref "IC203") (pin "8") (pinfunction "C_8") (pintype "passive"))
      (node (ref "R209") (pin "2") (pinfunction "2_2") (pintype "passive"))
    )
    (net (code "85") (name "Net-(IC204A-C)") (class "Default")
      (node (ref "IC204") (pin "2") (pinfunction "C_2") (pintype "passive"))
      (node (ref "R216") (pin "2") (pinfunction "2_2") (pintype "passive"))
    )
    (net (code "86") (name "Net-(IC204B-C)") (class "Default")
      (node (ref "IC204") (pin "4") (pinfunction "C_4") (pintype "passive"))
      (node (ref "R215") (pin "2") (pinfunction "2_2") (pintype "passive"))
    )
    (net (code "87") (name "Net-(IC204C-C)") (class "Default")
      (node (ref "IC204") (pin "6") (pinfunction "C_6") (pintype "passive"))
      (node (ref "R214") (pin "2") (pinfunction "2_2") (pintype "passive"))
    )
    (net (code "88") (name "Net-(IC204D-C)") (class "Default")
      (node (ref "IC204") (pin "8") (pinfunction "C_8") (pintype "passive"))
      (node (ref "R213") (pin "2") (pinfunction "2_2") (pintype "passive"))
    )
    (net (code "89") (name "Net-(LED1-PadA)") (class "Default")
      (node (ref "LED1") (pin "A") (pinfunction "A_A") (pintype "passive"))
      (node (ref "R2") (pin "1") (pinfunction "1_1") (pintype "passive"))
    )
    (net (code "90") (name "Net-(V1-+VIN)") (class "Default")
      (node (ref "D3") (pin "C") (pinfunction "C_C") (pintype "passive"))
      (node (ref "V1") (pin "2") (pinfunction "+VIN_2") (pintype "passive"))
    )
    (net (code "91") (name "Net-(V1--VIN)") (class "Default")
      (node (ref "V1") (pin "1") (pinfunction "-VIN_1") (pintype "passive"))
      (node (ref "X5") (pin "A2") (pinfunction "A_A2") (pintype "passive"))
      (node (ref "X5") (pin "B2") (pinfunction "A_B2") (pintype "passive"))
    )
    (net (code "92") (name "SCL") (class "Default")
      (node (ref "IC101") (pin "1") (pinfunction "(T0/XCK)PB0_1") (pintype "bidirectional"))
      (node (ref "IC102") (pin "6") (pinfunction "SCL_6") (pintype "bidirectional"))
    )
    (net (code "93") (name "SDA") (class "Default")
      (node (ref "IC101") (pin "2") (pinfunction "(T1)PB1_2") (pintype "bidirectional"))
      (node (ref "IC102") (pin "5") (pinfunction "SDA_5") (pintype "bidirectional"))
    )
    (net (code "94") (name "VCC") (class "Default")
      (node (ref "C1") (pin "1") (pinfunction "1_1") (pintype "passive"))
      (node (ref "D1") (pin "C") (pinfunction "C_C") (pintype "passive"))
      (node (ref "D2") (pin "C") (pinfunction "C_C") (pintype "passive"))
      (node (ref "IC102") (pin "8") (pinfunction "VCC_8") (pintype "power_in"))
    )
    (net (code "95") (name "unconnected-(IC101-AREF-Pad32)") (class "Default")
      (node (ref "IC101") (pin "32") (pinfunction "AREF_32") (pintype "passive"))
    )
    (net (code "96") (name "unconnected-(IC101-XTAL1-Pad13)") (class "Default")
      (node (ref "IC101") (pin "13") (pinfunction "XTAL1_13") (pintype "bidirectional"))
    )
    (net (code "97") (name "unconnected-(IC101-XTAL2-Pad12)") (class "Default")
      (node (ref "IC101") (pin "12") (pinfunction "XTAL2_12") (pintype "bidirectional"))
    )
    (net (code "98") (name "~{R}") (class "Default")
      (node (ref "IC101") (pin "21") (pinfunction "(OC2)PD7_21") (pintype "bidirectional"))
      (node (ref "X1") (pin "5") (pinfunction "A_5") (pintype "passive"))
      (node (ref "X1") (pin "6") (pinfunction "A_6") (pintype "passive"))
    )
  )
)
